# connectors.net
KiCad netlist of a schematic drawn in Altium Designer
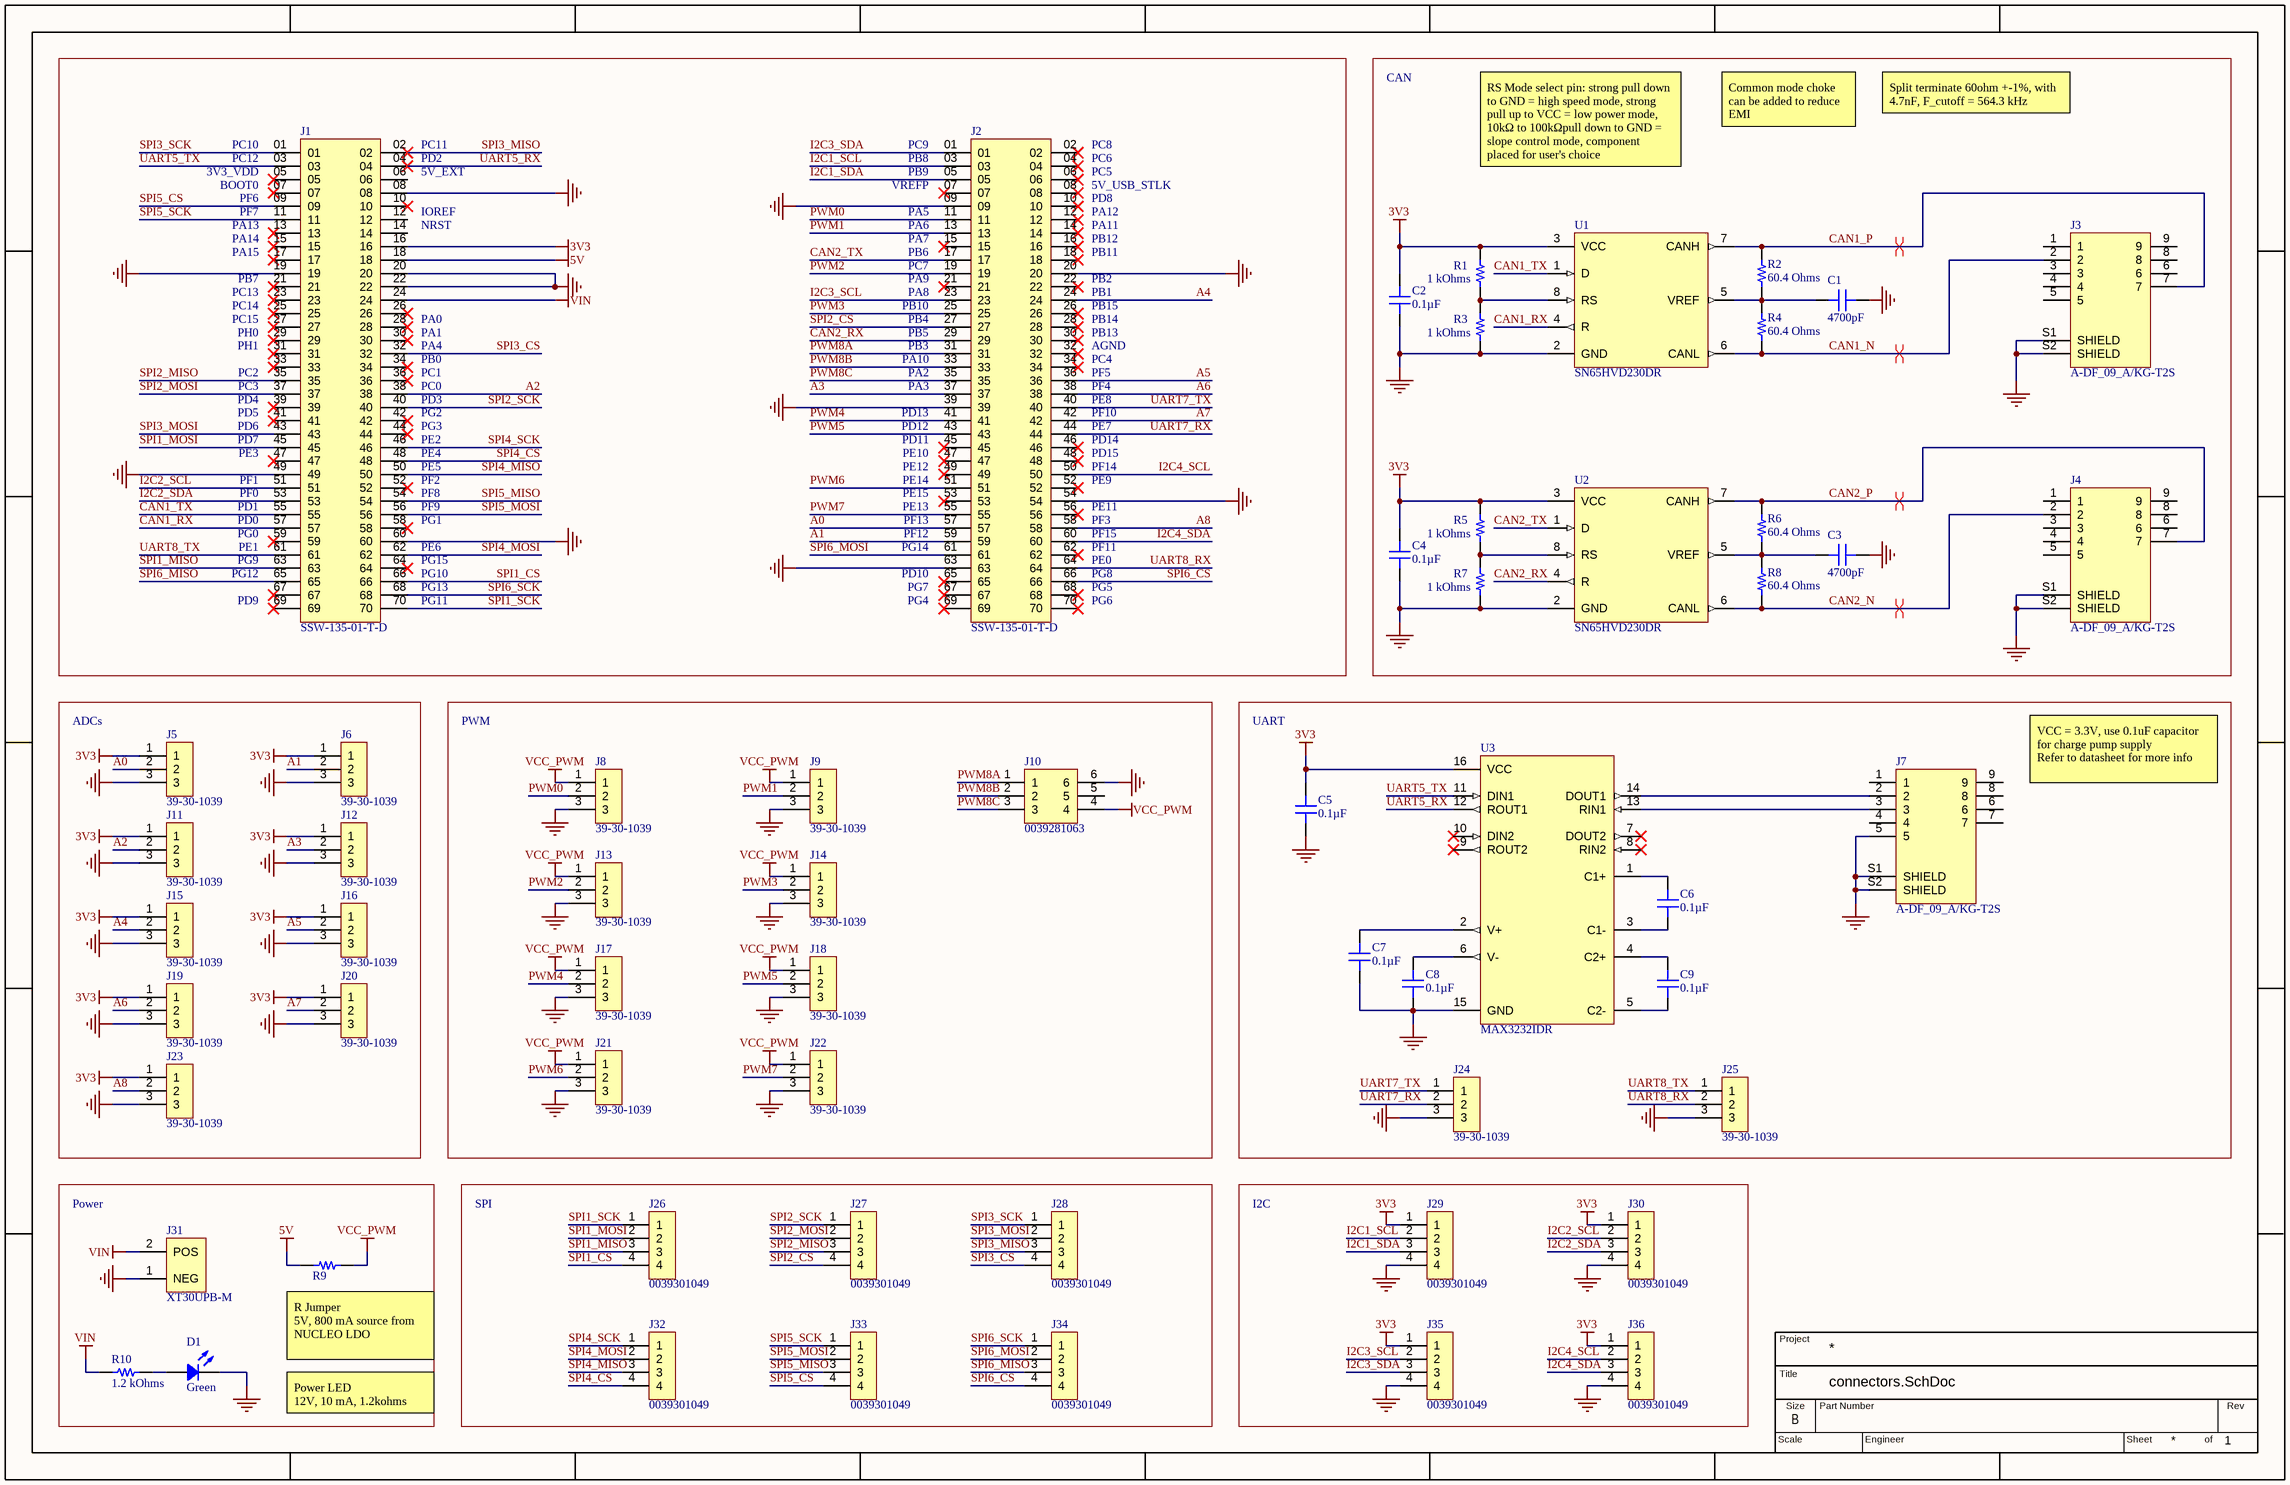
[diagram p0: connectors.SchDoc]

(export (version "E")
  (design (tool "Eeschema 10.0.6"))
  (components
    (comp (ref "C1")
      (value "4700pF")
      (footprint "CAP 0603_1608")
      (description "CAP CER 4700PF 50V X7R 0603")
      (fields
        (field (name "PART NUMBER") "CGA3E2X7R1H472K080AA")
        (field (name "MANUFACTURER") "TDK Corporation")
      )
      (libsource (lib "Celestial Altium Library - altium_library") (part "Capacitor"))
    )
    (comp (ref "C2")
      (value "0.1µF")
      (footprint "CAP 0603_1608")
      (description "CAP CER 0.1UF 25V X7R 0603")
      (fields
        (field (name "PART NUMBER") "CL10B104KA8NNNC")
        (field (name "MANUFACTURER") "Samsung Electro-Mechanics")
      )
      (libsource (lib "Celestial Altium Library - altium_library") (part "Capacitor"))
    )
    (comp (ref "C3")
      (value "4700pF")
      (footprint "CAP 0603_1608")
      (description "CAP CER 4700PF 50V X7R 0603")
      (fields
        (field (name "PART NUMBER") "CGA3E2X7R1H472K080AA")
        (field (name "MANUFACTURER") "TDK Corporation")
      )
      (libsource (lib "Celestial Altium Library - altium_library") (part "Capacitor"))
    )
    (comp (ref "C4")
      (value "0.1µF")
      (footprint "CAP 0603_1608")
      (description "CAP CER 0.1UF 25V X7R 0603")
      (fields
        (field (name "PART NUMBER") "CL10B104KA8NNNC")
        (field (name "MANUFACTURER") "Samsung Electro-Mechanics")
      )
      (libsource (lib "Celestial Altium Library - altium_library") (part "Capacitor"))
    )
    (comp (ref "C5")
      (value "0.1µF")
      (footprint "CAP 0603_1608")
      (description "CAP CER 0.1UF 25V X7R 0603")
      (fields
        (field (name "PART NUMBER") "CL10B104KA8NNNC")
        (field (name "MANUFACTURER") "Samsung Electro-Mechanics")
      )
      (libsource (lib "Celestial Altium Library - altium_library") (part "Capacitor"))
    )
    (comp (ref "C6")
      (value "0.1µF")
      (footprint "CAP 0603_1608")
      (description "CAP CER 0.1UF 25V X7R 0603")
      (fields
        (field (name "PART NUMBER") "CL10B104KA8NNNC")
        (field (name "MANUFACTURER") "Samsung Electro-Mechanics")
      )
      (libsource (lib "Celestial Altium Library - altium_library") (part "Capacitor"))
    )
    (comp (ref "C7")
      (value "0.1µF")
      (footprint "CAP 0603_1608")
      (description "CAP CER 0.1UF 25V X7R 0603")
      (fields
        (field (name "PART NUMBER") "CL10B104KA8NNNC")
        (field (name "MANUFACTURER") "Samsung Electro-Mechanics")
      )
      (libsource (lib "Celestial Altium Library - altium_library") (part "Capacitor"))
    )
    (comp (ref "C8")
      (value "0.1µF")
      (footprint "CAP 0603_1608")
      (description "CAP CER 0.1UF 25V X7R 0603")
      (fields
        (field (name "PART NUMBER") "CL10B104KA8NNNC")
        (field (name "MANUFACTURER") "Samsung Electro-Mechanics")
      )
      (libsource (lib "Celestial Altium Library - altium_library") (part "Capacitor"))
    )
    (comp (ref "C9")
      (value "0.1µF")
      (footprint "CAP 0603_1608")
      (description "CAP CER 0.1UF 25V X7R 0603")
      (fields
        (field (name "PART NUMBER") "CL10B104KA8NNNC")
        (field (name "MANUFACTURER") "Samsung Electro-Mechanics")
      )
      (libsource (lib "Celestial Altium Library - altium_library") (part "Capacitor"))
    )
    (comp (ref "D1")
      (value "Green")
      (footprint "LED 0805_2012 GREEN")
      (description "LED GREEN CLEAR SMD")
      (fields (field (name "PART NUMBER") "LTST-C170GKT") (field (name "MANUFACTURER") "Lite-On Inc."))
      (libsource (lib "Celestial Altium Library - altium_library") (part "LED"))
    )
    (comp (ref "J1")
      (value "SSW-135-01-T-D")
      (footprint "SAMTEC_SSW-135-01-T-D")
      (fields (field (name "MF") "Samtec"))
      (libsource (lib "ertc_symbols") (part "SSW-135-01-T-D"))
    )
    (comp (ref "J2")
      (value "SSW-135-01-T-D")
      (footprint "SAMTEC_SSW-135-01-T-D")
      (fields (field (name "MF") "Samtec"))
      (libsource (lib "ertc_symbols") (part "SSW-135-01-T-D"))
    )
    (comp (ref "J3")
      (value "A-DF_09_A/KG-T2S")
      (footprint "ASSMANN_A-DF09A/KG-T2S")
      (description "9 Position D-Sub Receptacle, Female Sockets Connector")
      (fields (field (name "MP") "A-DF 09 A/KG-T2S") (field (name "MF") "Assmann WSW"))
      (libsource (lib "ertc_symbols") (part "A-DF_09_A/KG-T2S"))
    )
    (comp (ref "J4")
      (value "A-DF_09_A/KG-T2S")
      (footprint "ASSMANN_A-DF09A/KG-T2S")
      (description "9 Position D-Sub Receptacle, Female Sockets Connector")
      (fields (field (name "MP") "A-DF 09 A/KG-T2S") (field (name "MF") "Assmann WSW"))
      (libsource (lib "ertc_symbols") (part "A-DF_09_A/KG-T2S"))
    )
    (comp (ref "J5")
      (value "39-30-1039")
      (footprint "MOLEX_39-30-1039")
      (description "Connector Header Through Hole 3 position 0.165 _4.20mm_")
      (fields (field (name "MP") "39301039") (field (name "MF") "Molex"))
      (libsource (lib "ertc_symbols") (part "39-30-1039"))
    )
    (comp (ref "J6")
      (value "39-30-1039")
      (footprint "MOLEX_39-30-1039")
      (description "Connector Header Through Hole 3 position 0.165 _4.20mm_")
      (fields (field (name "MP") "39301039") (field (name "MF") "Molex"))
      (libsource (lib "ertc_symbols") (part "39-30-1039"))
    )
    (comp (ref "J7")
      (value "A-DF_09_A/KG-T2S")
      (footprint "ASSMANN_A-DF09A/KG-T2S")
      (description "9 Position D-Sub Receptacle, Female Sockets Connector")
      (fields (field (name "MP") "A-DF 09 A/KG-T2S") (field (name "MF") "Assmann WSW"))
      (libsource (lib "ertc_symbols") (part "A-DF_09_A/KG-T2S"))
    )
    (comp (ref "J8")
      (value "39-30-1039")
      (footprint "MOLEX_39-30-1039")
      (description "Connector Header Through Hole 3 position 0.165 _4.20mm_")
      (fields (field (name "MP") "39301039") (field (name "MF") "Molex"))
      (libsource (lib "ertc_symbols") (part "39-30-1039"))
    )
    (comp (ref "J9")
      (value "39-30-1039")
      (footprint "MOLEX_39-30-1039")
      (description "Connector Header Through Hole 3 position 0.165 _4.20mm_")
      (fields (field (name "MP") "39301039") (field (name "MF") "Molex"))
      (libsource (lib "ertc_symbols") (part "39-30-1039"))
    )
    (comp (ref "J10")
      (value "0039281063")
      (footprint "MOLEX_0039281063")
      (description "Connector Header Through Hole, 6 position 0.165 (4.20mm)")
      (fields (field (name "MP") "0026013115") (field (name "MF") "Molex"))
      (libsource (lib "ertc_symbols") (part "0039281063"))
    )
    (comp (ref "J11")
      (value "39-30-1039")
      (footprint "MOLEX_39-30-1039")
      (description "Connector Header Through Hole 3 position 0.165 _4.20mm_")
      (fields (field (name "MP") "39301039") (field (name "MF") "Molex"))
      (libsource (lib "ertc_symbols") (part "39-30-1039"))
    )
    (comp (ref "J12")
      (value "39-30-1039")
      (footprint "MOLEX_39-30-1039")
      (description "Connector Header Through Hole 3 position 0.165 _4.20mm_")
      (fields (field (name "MP") "39301039") (field (name "MF") "Molex"))
      (libsource (lib "ertc_symbols") (part "39-30-1039"))
    )
    (comp (ref "J13")
      (value "39-30-1039")
      (footprint "MOLEX_39-30-1039")
      (description "Connector Header Through Hole 3 position 0.165 _4.20mm_")
      (fields (field (name "MP") "39301039") (field (name "MF") "Molex"))
      (libsource (lib "ertc_symbols") (part "39-30-1039"))
    )
    (comp (ref "J14")
      (value "39-30-1039")
      (footprint "MOLEX_39-30-1039")
      (description "Connector Header Through Hole 3 position 0.165 _4.20mm_")
      (fields (field (name "MP") "39301039") (field (name "MF") "Molex"))
      (libsource (lib "ertc_symbols") (part "39-30-1039"))
    )
    (comp (ref "J15")
      (value "39-30-1039")
      (footprint "MOLEX_39-30-1039")
      (description "Connector Header Through Hole 3 position 0.165 _4.20mm_")
      (fields (field (name "MP") "39301039") (field (name "MF") "Molex"))
      (libsource (lib "ertc_symbols") (part "39-30-1039"))
    )
    (comp (ref "J16")
      (value "39-30-1039")
      (footprint "MOLEX_39-30-1039")
      (description "Connector Header Through Hole 3 position 0.165 _4.20mm_")
      (fields (field (name "MP") "39301039") (field (name "MF") "Molex"))
      (libsource (lib "ertc_symbols") (part "39-30-1039"))
    )
    (comp (ref "J17")
      (value "39-30-1039")
      (footprint "MOLEX_39-30-1039")
      (description "Connector Header Through Hole 3 position 0.165 _4.20mm_")
      (fields (field (name "MP") "39301039") (field (name "MF") "Molex"))
      (libsource (lib "ertc_symbols") (part "39-30-1039"))
    )
    (comp (ref "J18")
      (value "39-30-1039")
      (footprint "MOLEX_39-30-1039")
      (description "Connector Header Through Hole 3 position 0.165 _4.20mm_")
      (fields (field (name "MP") "39301039") (field (name "MF") "Molex"))
      (libsource (lib "ertc_symbols") (part "39-30-1039"))
    )
    (comp (ref "J19")
      (value "39-30-1039")
      (footprint "MOLEX_39-30-1039")
      (description "Connector Header Through Hole 3 position 0.165 _4.20mm_")
      (fields (field (name "MP") "39301039") (field (name "MF") "Molex"))
      (libsource (lib "ertc_symbols") (part "39-30-1039"))
    )
    (comp (ref "J20")
      (value "39-30-1039")
      (footprint "MOLEX_39-30-1039")
      (description "Connector Header Through Hole 3 position 0.165 _4.20mm_")
      (fields (field (name "MP") "39301039") (field (name "MF") "Molex"))
      (libsource (lib "ertc_symbols") (part "39-30-1039"))
    )
    (comp (ref "J21")
      (value "39-30-1039")
      (footprint "MOLEX_39-30-1039")
      (description "Connector Header Through Hole 3 position 0.165 _4.20mm_")
      (fields (field (name "MP") "39301039") (field (name "MF") "Molex"))
      (libsource (lib "ertc_symbols") (part "39-30-1039"))
    )
    (comp (ref "J22")
      (value "39-30-1039")
      (footprint "MOLEX_39-30-1039")
      (description "Connector Header Through Hole 3 position 0.165 _4.20mm_")
      (fields (field (name "MP") "39301039") (field (name "MF") "Molex"))
      (libsource (lib "ertc_symbols") (part "39-30-1039"))
    )
    (comp (ref "J23")
      (value "39-30-1039")
      (footprint "MOLEX_39-30-1039")
      (description "Connector Header Through Hole 3 position 0.165 _4.20mm_")
      (fields (field (name "MP") "39301039") (field (name "MF") "Molex"))
      (libsource (lib "ertc_symbols") (part "39-30-1039"))
    )
    (comp (ref "J24")
      (value "39-30-1039")
      (footprint "MOLEX_39-30-1039")
      (description "Connector Header Through Hole 3 position 0.165 _4.20mm_")
      (fields (field (name "MP") "39301039") (field (name "MF") "Molex"))
      (libsource (lib "ertc_symbols") (part "39-30-1039"))
    )
    (comp (ref "J25")
      (value "39-30-1039")
      (footprint "MOLEX_39-30-1039")
      (description "Connector Header Through Hole 3 position 0.165 _4.20mm_")
      (fields (field (name "MP") "39301039") (field (name "MF") "Molex"))
      (libsource (lib "ertc_symbols") (part "39-30-1039"))
    )
    (comp (ref "J26")
      (value "0039301049")
      (footprint "MOLEX_0039301049")
      (description "Connector Header Through Hole 4 position 0.165 _4.20mm_")
      (fields (field (name "MF") "Molex"))
      (libsource (lib "ertc_symbols") (part "0039301049"))
    )
    (comp (ref "J27")
      (value "0039301049")
      (footprint "MOLEX_0039301049")
      (description "Connector Header Through Hole 4 position 0.165 _4.20mm_")
      (fields (field (name "MF") "Molex"))
      (libsource (lib "ertc_symbols") (part "0039301049"))
    )
    (comp (ref "J28")
      (value "0039301049")
      (footprint "MOLEX_0039301049")
      (description "Connector Header Through Hole 4 position 0.165 _4.20mm_")
      (fields (field (name "MF") "Molex"))
      (libsource (lib "ertc_symbols") (part "0039301049"))
    )
    (comp (ref "J29")
      (value "0039301049")
      (footprint "MOLEX_0039301049")
      (description "Connector Header Through Hole 4 position 0.165 _4.20mm_")
      (fields (field (name "MF") "Molex"))
      (libsource (lib "ertc_symbols") (part "0039301049"))
    )
    (comp (ref "J30")
      (value "0039301049")
      (footprint "MOLEX_0039301049")
      (description "Connector Header Through Hole 4 position 0.165 _4.20mm_")
      (fields (field (name "MF") "Molex"))
      (libsource (lib "ertc_symbols") (part "0039301049"))
    )
    (comp (ref "J31")
      (value "XT30UPB-M")
      (footprint "AMASS_XT30-M")
      (description "Plug; DC supply; XT60; male; PIN: 2; for cable; soldered; 30A; 500V")
      (fields (field (name "MP") "XT60-M") (field (name "MF") "AMASS"))
      (libsource (lib "ertc_symbols") (part "XT30UPB-M"))
    )
    (comp (ref "J32")
      (value "0039301049")
      (footprint "MOLEX_0039301049")
      (description "Connector Header Through Hole 4 position 0.165 _4.20mm_")
      (fields (field (name "MF") "Molex"))
      (libsource (lib "ertc_symbols") (part "0039301049"))
    )
    (comp (ref "J33")
      (value "0039301049")
      (footprint "MOLEX_0039301049")
      (description "Connector Header Through Hole 4 position 0.165 _4.20mm_")
      (fields (field (name "MF") "Molex"))
      (libsource (lib "ertc_symbols") (part "0039301049"))
    )
    (comp (ref "J34")
      (value "0039301049")
      (footprint "MOLEX_0039301049")
      (description "Connector Header Through Hole 4 position 0.165 _4.20mm_")
      (fields (field (name "MF") "Molex"))
      (libsource (lib "ertc_symbols") (part "0039301049"))
    )
    (comp (ref "J35")
      (value "0039301049")
      (footprint "MOLEX_0039301049")
      (description "Connector Header Through Hole 4 position 0.165 _4.20mm_")
      (fields (field (name "MF") "Molex"))
      (libsource (lib "ertc_symbols") (part "0039301049"))
    )
    (comp (ref "J36")
      (value "0039301049")
      (footprint "MOLEX_0039301049")
      (description "Connector Header Through Hole 4 position 0.165 _4.20mm_")
      (fields (field (name "MF") "Molex"))
      (libsource (lib "ertc_symbols") (part "0039301049"))
    )
    (comp (ref "R1")
      (value "1 kOhms")
      (footprint "RES 0805_2012")
      (description "RES 1K OHM 1% 1/4W 0805")
      (fields
        (field (name "PART NUMBER") "RNCP0805FTD1K00")
        (field (name "MANUFACTURER") "Stackpole Electronics Inc")
      )
      (libsource (lib "Celestial Altium Library - altium_library") (part "Resistor"))
    )
    (comp (ref "R2")
      (value "60.4 Ohms")
      (footprint "RES 0603_1608")
      (description "RES 60.4 OHM 1% 1/10W 0603")
      (fields
        (field (name "PART NUMBER") "RMCF0603FT60R4")
        (field (name "MANUFACTURER") "Stackpole Electronics Inc")
      )
      (libsource (lib "Celestial Altium Library - altium_library") (part "Resistor"))
    )
    (comp (ref "R3")
      (value "1 kOhms")
      (footprint "RES 0805_2012")
      (description "RES 1K OHM 1% 1/4W 0805")
      (fields
        (field (name "PART NUMBER") "RNCP0805FTD1K00")
        (field (name "MANUFACTURER") "Stackpole Electronics Inc")
      )
      (libsource (lib "Celestial Altium Library - altium_library") (part "Resistor"))
    )
    (comp (ref "R4")
      (value "60.4 Ohms")
      (footprint "RES 0603_1608")
      (description "RES 60.4 OHM 1% 1/10W 0603")
      (fields
        (field (name "PART NUMBER") "RMCF0603FT60R4")
        (field (name "MANUFACTURER") "Stackpole Electronics Inc")
      )
      (libsource (lib "Celestial Altium Library - altium_library") (part "Resistor"))
    )
    (comp (ref "R5")
      (value "1 kOhms")
      (footprint "RES 0805_2012")
      (description "RES 1K OHM 1% 1/4W 0805")
      (fields
        (field (name "PART NUMBER") "RNCP0805FTD1K00")
        (field (name "MANUFACTURER") "Stackpole Electronics Inc")
      )
      (libsource (lib "Celestial Altium Library - altium_library") (part "Resistor"))
    )
    (comp (ref "R6")
      (value "60.4 Ohms")
      (footprint "RES 0603_1608")
      (description "RES 60.4 OHM 1% 1/10W 0603")
      (fields
        (field (name "PART NUMBER") "RMCF0603FT60R4")
        (field (name "MANUFACTURER") "Stackpole Electronics Inc")
      )
      (libsource (lib "Celestial Altium Library - altium_library") (part "Resistor"))
    )
    (comp (ref "R7")
      (value "1 kOhms")
      (footprint "RES 0805_2012")
      (description "RES 1K OHM 1% 1/4W 0805")
      (fields
        (field (name "PART NUMBER") "RNCP0805FTD1K00")
        (field (name "MANUFACTURER") "Stackpole Electronics Inc")
      )
      (libsource (lib "Celestial Altium Library - altium_library") (part "Resistor"))
    )
    (comp (ref "R8")
      (value "60.4 Ohms")
      (footprint "RES 0603_1608")
      (description "RES 60.4 OHM 1% 1/10W 0603")
      (fields
        (field (name "PART NUMBER") "RMCF0603FT60R4")
        (field (name "MANUFACTURER") "Stackpole Electronics Inc")
      )
      (libsource (lib "Celestial Altium Library - altium_library") (part "Resistor"))
    )
    (comp (ref "R9")
      (value "~")
      (footprint "RES 0603_1608")
      (description "RES SMD 0 OHM JUMP 1/10W 0603")
      (fields (field (name "PART NUMBER") "CRCW06030000Z0EBC") (field (name "MANUFACTURER") "Vishay Dale"))
      (libsource (lib "Celestial Altium Library - altium_library") (part "Resistor"))
    )
    (comp (ref "R10")
      (value "1.2 kOhms")
      (footprint "RES 0603_1608")
      (description "CRGCQ 0603 1K2 1%")
      (fields
        (field (name "PART NUMBER") "CRGCQ0603F1K2")
        (field (name "MANUFACTURER") "TE Connectivity Passive Product")
      )
      (libsource (lib "Celestial Altium Library - altium_library") (part "Resistor"))
    )
    (comp (ref "U1")
      (value "SN65HVD230DR")
      (footprint "SOIC127P599X175-8N")
      (description "3.3 V CAN Transceiver with Standby Mode 8-SOIC -40 to 85")
      (fields (field (name "MF") "Texas Instruments"))
      (libsource (lib "ertc_symbols") (part "SN65HVD230DR"))
    )
    (comp (ref "U2")
      (value "SN65HVD230DR")
      (footprint "SOIC127P599X175-8N")
      (description "3.3 V CAN Transceiver with Standby Mode 8-SOIC -40 to 85")
      (fields (field (name "MF") "Texas Instruments"))
      (libsource (lib "ertc_symbols") (part "SN65HVD230DR"))
    )
    (comp (ref "U3")
      (value "MAX3232IDR")
      (footprint "SOIC127P600X175-16N")
      (description "3-V to 5.5-V multichannel RS-232 line driver & receiver 16-SOIC -40 to 85")
      (fields (field (name "MF") "Texas Instruments") (field (name "DIGI-KEY_PART_NUMBER") "296-13098-1-ND"))
      (libsource (lib "ertc_symbols") (part "MAX3232IDR"))
    )
  )
  (nets
    (net (code "2") (name "/A0") (class "Default")
      (node (ref "J2") (pin "57") (pinfunction "57_57") (pintype "passive"))
      (node (ref "J5") (pin "2") (pinfunction "2_2") (pintype "passive"))
    )
    (net (code "3") (name "/A1") (class "Default")
      (node (ref "J2") (pin "59") (pinfunction "59_59") (pintype "passive"))
      (node (ref "J6") (pin "2") (pinfunction "2_2") (pintype "passive"))
    )
    (net (code "4") (name "/A2") (class "Default")
      (node (ref "J1") (pin "38") (pinfunction "38_38") (pintype "passive"))
      (node (ref "J11") (pin "2") (pinfunction "2_2") (pintype "passive"))
    )
    (net (code "5") (name "/A3") (class "Default")
      (node (ref "J12") (pin "2") (pinfunction "2_2") (pintype "passive"))
      (node (ref "J2") (pin "37") (pinfunction "37_37") (pintype "passive"))
    )
    (net (code "6") (name "/A4") (class "Default")
      (node (ref "J15") (pin "2") (pinfunction "2_2") (pintype "passive"))
      (node (ref "J2") (pin "24") (pinfunction "24_24") (pintype "passive"))
    )
    (net (code "7") (name "/A5") (class "Default")
      (node (ref "J16") (pin "2") (pinfunction "2_2") (pintype "passive"))
      (node (ref "J2") (pin "36") (pinfunction "36_36") (pintype "passive"))
    )
    (net (code "8") (name "/A6") (class "Default")
      (node (ref "J19") (pin "2") (pinfunction "2_2") (pintype "passive"))
      (node (ref "J2") (pin "38") (pinfunction "38_38") (pintype "passive"))
    )
    (net (code "9") (name "/A7") (class "Default")
      (node (ref "J2") (pin "42") (pinfunction "42_42") (pintype "passive"))
      (node (ref "J20") (pin "2") (pinfunction "2_2") (pintype "passive"))
    )
    (net (code "10") (name "/A8") (class "Default")
      (node (ref "J2") (pin "58") (pinfunction "58_58") (pintype "passive"))
      (node (ref "J23") (pin "2") (pinfunction "2_2") (pintype "passive"))
    )
    (net (code "11") (name "/CAN1_N") (class "Default")
      (node (ref "J3") (pin "2") (pinfunction "2_2") (pintype "passive"))
      (node (ref "R4") (pin "2") (pinfunction "2_2") (pintype "passive"))
      (node (ref "U1") (pin "6") (pinfunction "CANL_6") (pintype "output"))
    )
    (net (code "12") (name "/CAN1_P") (class "Default")
      (node (ref "J3") (pin "7") (pinfunction "7_7") (pintype "passive"))
      (node (ref "R2") (pin "1") (pinfunction "1_1") (pintype "passive"))
      (node (ref "U1") (pin "7") (pinfunction "CANH_7") (pintype "output"))
    )
    (net (code "13") (name "/CAN1_RX") (class "Default")
      (node (ref "J1") (pin "57") (pinfunction "57_57") (pintype "passive"))
      (node (ref "U1") (pin "4") (pinfunction "R_4") (pintype "output"))
    )
    (net (code "14") (name "/CAN1_TX") (class "Default")
      (node (ref "J1") (pin "55") (pinfunction "55_55") (pintype "passive"))
      (node (ref "U1") (pin "1") (pinfunction "D_1") (pintype "input"))
    )
    (net (code "15") (name "/CAN2_N") (class "Default")
      (node (ref "J4") (pin "2") (pinfunction "2_2") (pintype "passive"))
      (node (ref "R8") (pin "2") (pinfunction "2_2") (pintype "passive"))
      (node (ref "U2") (pin "6") (pinfunction "CANL_6") (pintype "output"))
    )
    (net (code "16") (name "/CAN2_P") (class "Default")
      (node (ref "J4") (pin "7") (pinfunction "7_7") (pintype "passive"))
      (node (ref "R6") (pin "1") (pinfunction "1_1") (pintype "passive"))
      (node (ref "U2") (pin "7") (pinfunction "CANH_7") (pintype "output"))
    )
    (net (code "17") (name "/CAN2_RX") (class "Default")
      (node (ref "J2") (pin "29") (pinfunction "29_29") (pintype "passive"))
      (node (ref "U2") (pin "4") (pinfunction "R_4") (pintype "output"))
    )
    (net (code "18") (name "/CAN2_TX") (class "Default")
      (node (ref "J2") (pin "17") (pinfunction "17_17") (pintype "passive"))
      (node (ref "U2") (pin "1") (pinfunction "D_1") (pintype "input"))
    )
    (net (code "19") (name "/I2C1_SCL") (class "Default")
      (node (ref "J2") (pin "03") (pinfunction "03_03") (pintype "passive"))
      (node (ref "J29") (pin "2") (pinfunction "2_2") (pintype "passive"))
    )
    (net (code "20") (name "/I2C1_SDA") (class "Default")
      (node (ref "J2") (pin "05") (pinfunction "05_05") (pintype "passive"))
      (node (ref "J29") (pin "3") (pinfunction "3_3") (pintype "passive"))
    )
    (net (code "21") (name "/I2C2_SCL") (class "Default")
      (node (ref "J1") (pin "51") (pinfunction "51_51") (pintype "passive"))
      (node (ref "J30") (pin "2") (pinfunction "2_2") (pintype "passive"))
    )
    (net (code "22") (name "/I2C2_SDA") (class "Default")
      (node (ref "J1") (pin "53") (pinfunction "53_53") (pintype "passive"))
      (node (ref "J30") (pin "3") (pinfunction "3_3") (pintype "passive"))
    )
    (net (code "23") (name "/I2C3_SCL") (class "Default")
      (node (ref "J2") (pin "23") (pinfunction "23_23") (pintype "passive"))
      (node (ref "J35") (pin "2") (pinfunction "2_2") (pintype "passive"))
    )
    (net (code "24") (name "/I2C3_SDA") (class "Default")
      (node (ref "J2") (pin "01") (pinfunction "01_01") (pintype "passive"))
      (node (ref "J35") (pin "3") (pinfunction "3_3") (pintype "passive"))
    )
    (net (code "25") (name "/I2C4_SCL") (class "Default")
      (node (ref "J2") (pin "50") (pinfunction "50_50") (pintype "passive"))
      (node (ref "J36") (pin "2") (pinfunction "2_2") (pintype "passive"))
    )
    (net (code "26") (name "/I2C4_SDA") (class "Default")
      (node (ref "J2") (pin "60") (pinfunction "60_60") (pintype "passive"))
      (node (ref "J36") (pin "3") (pinfunction "3_3") (pintype "passive"))
    )
    (net (code "27") (name "/PWM0") (class "Default")
      (node (ref "J2") (pin "11") (pinfunction "11_11") (pintype "passive"))
      (node (ref "J8") (pin "2") (pinfunction "2_2") (pintype "passive"))
    )
    (net (code "28") (name "/PWM1") (class "Default")
      (node (ref "J2") (pin "13") (pinfunction "13_13") (pintype "passive"))
      (node (ref "J9") (pin "2") (pinfunction "2_2") (pintype "passive"))
    )
    (net (code "29") (name "/PWM2") (class "Default")
      (node (ref "J13") (pin "2") (pinfunction "2_2") (pintype "passive"))
      (node (ref "J2") (pin "19") (pinfunction "19_19") (pintype "passive"))
    )
    (net (code "30") (name "/PWM3") (class "Default")
      (node (ref "J14") (pin "2") (pinfunction "2_2") (pintype "passive"))
      (node (ref "J2") (pin "25") (pinfunction "25_25") (pintype "passive"))
    )
    (net (code "31") (name "/PWM4") (class "Default")
      (node (ref "J17") (pin "2") (pinfunction "2_2") (pintype "passive"))
      (node (ref "J2") (pin "41") (pinfunction "41_41") (pintype "passive"))
    )
    (net (code "32") (name "/PWM5") (class "Default")
      (node (ref "J18") (pin "2") (pinfunction "2_2") (pintype "passive"))
      (node (ref "J2") (pin "43") (pinfunction "43_43") (pintype "passive"))
    )
    (net (code "33") (name "/PWM6") (class "Default")
      (node (ref "J2") (pin "51") (pinfunction "51_51") (pintype "passive"))
      (node (ref "J21") (pin "2") (pinfunction "2_2") (pintype "passive"))
    )
    (net (code "34") (name "/PWM7") (class "Default")
      (node (ref "J2") (pin "55") (pinfunction "55_55") (pintype "passive"))
      (node (ref "J22") (pin "2") (pinfunction "2_2") (pintype "passive"))
    )
    (net (code "35") (name "/PWM8A") (class "Default")
      (node (ref "J10") (pin "1") (pinfunction "1_1") (pintype "passive"))
      (node (ref "J2") (pin "31") (pinfunction "31_31") (pintype "passive"))
    )
    (net (code "36") (name "/PWM8B") (class "Default")
      (node (ref "J10") (pin "2") (pinfunction "2_2") (pintype "passive"))
      (node (ref "J2") (pin "33") (pinfunction "33_33") (pintype "passive"))
    )
    (net (code "37") (name "/PWM8C") (class "Default")
      (node (ref "J10") (pin "3") (pinfunction "3_3") (pintype "passive"))
      (node (ref "J2") (pin "35") (pinfunction "35_35") (pintype "passive"))
    )
    (net (code "38") (name "/SPI1_CS") (class "Default")
      (node (ref "J1") (pin "66") (pinfunction "66_66") (pintype "passive"))
      (node (ref "J26") (pin "4") (pinfunction "4_4") (pintype "passive"))
    )
    (net (code "39") (name "/SPI1_MISO") (class "Default")
      (node (ref "J1") (pin "63") (pinfunction "63_63") (pintype "passive"))
      (node (ref "J26") (pin "3") (pinfunction "3_3") (pintype "passive"))
    )
    (net (code "40") (name "/SPI1_MOSI") (class "Default")
      (node (ref "J1") (pin "45") (pinfunction "45_45") (pintype "passive"))
      (node (ref "J26") (pin "2") (pinfunction "2_2") (pintype "passive"))
    )
    (net (code "41") (name "/SPI1_SCK") (class "Default")
      (node (ref "J1") (pin "70") (pinfunction "70_70") (pintype "passive"))
      (node (ref "J26") (pin "1") (pinfunction "1_1") (pintype "passive"))
    )
    (net (code "42") (name "/SPI2_CS") (class "Default")
      (node (ref "J2") (pin "27") (pinfunction "27_27") (pintype "passive"))
      (node (ref "J27") (pin "4") (pinfunction "4_4") (pintype "passive"))
    )
    (net (code "43") (name "/SPI2_MISO") (class "Default")
      (node (ref "J1") (pin "35") (pinfunction "35_35") (pintype "passive"))
      (node (ref "J27") (pin "3") (pinfunction "3_3") (pintype "passive"))
    )
    (net (code "44") (name "/SPI2_MOSI") (class "Default")
      (node (ref "J1") (pin "37") (pinfunction "37_37") (pintype "passive"))
      (node (ref "J27") (pin "2") (pinfunction "2_2") (pintype "passive"))
    )
    (net (code "45") (name "/SPI2_SCK") (class "Default")
      (node (ref "J1") (pin "40") (pinfunction "40_40") (pintype "passive"))
      (node (ref "J27") (pin "1") (pinfunction "1_1") (pintype "passive"))
    )
    (net (code "46") (name "/SPI3_CS") (class "Default")
      (node (ref "J1") (pin "32") (pinfunction "32_32") (pintype "passive"))
      (node (ref "J28") (pin "4") (pinfunction "4_4") (pintype "passive"))
    )
    (net (code "47") (name "/SPI3_MISO") (class "Default")
      (node (ref "J1") (pin "02") (pinfunction "02_02") (pintype "passive"))
      (node (ref "J28") (pin "3") (pinfunction "3_3") (pintype "passive"))
    )
    (net (code "48") (name "/SPI3_MOSI") (class "Default")
      (node (ref "J1") (pin "43") (pinfunction "43_43") (pintype "passive"))
      (node (ref "J28") (pin "2") (pinfunction "2_2") (pintype "passive"))
    )
    (net (code "49") (name "/SPI3_SCK") (class "Default")
      (node (ref "J1") (pin "01") (pinfunction "01_01") (pintype "passive"))
      (node (ref "J28") (pin "1") (pinfunction "1_1") (pintype "passive"))
    )
    (net (code "50") (name "/SPI4_CS") (class "Default")
      (node (ref "J1") (pin "48") (pinfunction "48_48") (pintype "passive"))
      (node (ref "J32") (pin "4") (pinfunction "4_4") (pintype "passive"))
    )
    (net (code "51") (name "/SPI4_MISO") (class "Default")
      (node (ref "J1") (pin "50") (pinfunction "50_50") (pintype "passive"))
      (node (ref "J32") (pin "3") (pinfunction "3_3") (pintype "passive"))
    )
    (net (code "52") (name "/SPI4_MOSI") (class "Default")
      (node (ref "J1") (pin "62") (pinfunction "62_62") (pintype "passive"))
      (node (ref "J32") (pin "2") (pinfunction "2_2") (pintype "passive"))
    )
    (net (code "53") (name "/SPI4_SCK") (class "Default")
      (node (ref "J1") (pin "46") (pinfunction "46_46") (pintype "passive"))
      (node (ref "J32") (pin "1") (pinfunction "1_1") (pintype "passive"))
    )
    (net (code "54") (name "/SPI5_CS") (class "Default")
      (node (ref "J1") (pin "09") (pinfunction "09_09") (pintype "passive"))
      (node (ref "J33") (pin "4") (pinfunction "4_4") (pintype "passive"))
    )
    (net (code "55") (name "/SPI5_MISO") (class "Default")
      (node (ref "J1") (pin "54") (pinfunction "54_54") (pintype "passive"))
      (node (ref "J33") (pin "3") (pinfunction "3_3") (pintype "passive"))
    )
    (net (code "56") (name "/SPI5_MOSI") (class "Default")
      (node (ref "J1") (pin "56") (pinfunction "56_56") (pintype "passive"))
      (node (ref "J33") (pin "2") (pinfunction "2_2") (pintype "passive"))
    )
    (net (code "57") (name "/SPI5_SCK") (class "Default")
      (node (ref "J1") (pin "11") (pinfunction "11_11") (pintype "passive"))
      (node (ref "J33") (pin "1") (pinfunction "1_1") (pintype "passive"))
    )
    (net (code "58") (name "/SPI6_CS") (class "Default")
      (node (ref "J2") (pin "66") (pinfunction "66_66") (pintype "passive"))
      (node (ref "J34") (pin "4") (pinfunction "4_4") (pintype "passive"))
    )
    (net (code "59") (name "/SPI6_MISO") (class "Default")
      (node (ref "J1") (pin "65") (pinfunction "65_65") (pintype "passive"))
      (node (ref "J34") (pin "3") (pinfunction "3_3") (pintype "passive"))
    )
    (net (code "60") (name "/SPI6_MOSI") (class "Default")
      (node (ref "J2") (pin "61") (pinfunction "61_61") (pintype "passive"))
      (node (ref "J34") (pin "2") (pinfunction "2_2") (pintype "passive"))
    )
    (net (code "61") (name "/SPI6_SCK") (class "Default")
      (node (ref "J1") (pin "68") (pinfunction "68_68") (pintype "passive"))
      (node (ref "J34") (pin "1") (pinfunction "1_1") (pintype "passive"))
    )
    (net (code "62") (name "/UART5_RX") (class "Default")
      (node (ref "J1") (pin "04") (pinfunction "04_04") (pintype "passive"))
      (node (ref "U3") (pin "12") (pinfunction "ROUT1_12") (pintype "output"))
    )
    (net (code "63") (name "/UART5_TX") (class "Default")
      (node (ref "J1") (pin "03") (pinfunction "03_03") (pintype "passive"))
      (node (ref "U3") (pin "11") (pinfunction "DIN1_11") (pintype "input"))
    )
    (net (code "64") (name "/UART7_RX") (class "Default")
      (node (ref "J2") (pin "44") (pinfunction "44_44") (pintype "passive"))
      (node (ref "J24") (pin "2") (pinfunction "2_2") (pintype "passive"))
    )
    (net (code "65") (name "/UART7_TX") (class "Default")
      (node (ref "J2") (pin "40") (pinfunction "40_40") (pintype "passive"))
      (node (ref "J24") (pin "1") (pinfunction "1_1") (pintype "passive"))
    )
    (net (code "66") (name "/UART8_RX") (class "Default")
      (node (ref "J2") (pin "64") (pinfunction "64_64") (pintype "passive"))
      (node (ref "J25") (pin "2") (pinfunction "2_2") (pintype "passive"))
    )
    (net (code "67") (name "/UART8_TX") (class "Default")
      (node (ref "J1") (pin "61") (pinfunction "61_61") (pintype "passive"))
      (node (ref "J25") (pin "1") (pinfunction "1_1") (pintype "passive"))
    )
    (net (code "68") (name "3V3") (class "Default")
      (node (ref "C2") (pin "2") (pinfunction "2_2") (pintype "passive"))
      (node (ref "C4") (pin "2") (pinfunction "2_2") (pintype "passive"))
      (node (ref "C5") (pin "2") (pinfunction "2_2") (pintype "passive"))
      (node (ref "J1") (pin "16") (pinfunction "16_16") (pintype "passive"))
      (node (ref "J11") (pin "1") (pinfunction "1_1") (pintype "passive"))
      (node (ref "J12") (pin "1") (pinfunction "1_1") (pintype "passive"))
      (node (ref "J15") (pin "1") (pinfunction "1_1") (pintype "passive"))
      (node (ref "J16") (pin "1") (pinfunction "1_1") (pintype "passive"))
      (node (ref "J19") (pin "1") (pinfunction "1_1") (pintype "passive"))
      (node (ref "J20") (pin "1") (pinfunction "1_1") (pintype "passive"))
      (node (ref "J23") (pin "1") (pinfunction "1_1") (pintype "passive"))
      (node (ref "J29") (pin "1") (pinfunction "1_1") (pintype "passive"))
      (node (ref "J30") (pin "1") (pinfunction "1_1") (pintype "passive"))
      (node (ref "J35") (pin "1") (pinfunction "1_1") (pintype "passive"))
      (node (ref "J36") (pin "1") (pinfunction "1_1") (pintype "passive"))
      (node (ref "J5") (pin "1") (pinfunction "1_1") (pintype "passive"))
      (node (ref "J6") (pin "1") (pinfunction "1_1") (pintype "passive"))
      (node (ref "R1") (pin "2") (pinfunction "2_2") (pintype "passive"))
      (node (ref "R5") (pin "2") (pinfunction "2_2") (pintype "passive"))
      (node (ref "U1") (pin "3") (pinfunction "VCC_3") (pintype "power_in"))
      (node (ref "U2") (pin "3") (pinfunction "VCC_3") (pintype "power_in"))
      (node (ref "U3") (pin "16") (pinfunction "VCC_16") (pintype "power_in"))
    )
    (net (code "69") (name "5V") (class "Default")
      (node (ref "J1") (pin "18") (pinfunction "18_18") (pintype "passive"))
      (node (ref "R9") (pin "1") (pinfunction "1_1") (pintype "passive"))
    )
    (net (code "70") (name "GND") (class "Default")
      (node (ref "C1") (pin "2") (pinfunction "2_2") (pintype "passive"))
      (node (ref "C2") (pin "1") (pinfunction "1_1") (pintype "passive"))
      (node (ref "C3") (pin "2") (pinfunction "2_2") (pintype "passive"))
      (node (ref "C4") (pin "1") (pinfunction "1_1") (pintype "passive"))
      (node (ref "C5") (pin "1") (pinfunction "1_1") (pintype "passive"))
      (node (ref "C7") (pin "1") (pinfunction "1_1") (pintype "passive"))
      (node (ref "C8") (pin "1") (pinfunction "1_1") (pintype "passive"))
      (node (ref "D1") (pin "2") (pinfunction "2_2") (pintype "passive"))
      (node (ref "J1") (pin "08") (pinfunction "08_08") (pintype "passive"))
      (node (ref "J1") (pin "19") (pinfunction "19_19") (pintype "passive"))
      (node (ref "J1") (pin "20") (pinfunction "20_20") (pintype "passive"))
      (node (ref "J1") (pin "22") (pinfunction "22_22") (pintype "passive"))
      (node (ref "J1") (pin "49") (pinfunction "49_49") (pintype "passive"))
      (node (ref "J1") (pin "60") (pinfunction "60_60") (pintype "passive"))
      (node (ref "J10") (pin "6") (pinfunction "6_6") (pintype "passive"))
      (node (ref "J11") (pin "3") (pinfunction "3_3") (pintype "passive"))
      (node (ref "J12") (pin "3") (pinfunction "3_3") (pintype "passive"))
      (node (ref "J13") (pin "3") (pinfunction "3_3") (pintype "passive"))
      (node (ref "J14") (pin "3") (pinfunction "3_3") (pintype "passive"))
      (node (ref "J15") (pin "3") (pinfunction "3_3") (pintype "passive"))
      (node (ref "J16") (pin "3") (pinfunction "3_3") (pintype "passive"))
      (node (ref "J17") (pin "3") (pinfunction "3_3") (pintype "passive"))
      (node (ref "J18") (pin "3") (pinfunction "3_3") (pintype "passive"))
      (node (ref "J19") (pin "3") (pinfunction "3_3") (pintype "passive"))
      (node (ref "J2") (pin "09") (pinfunction "09_09") (pintype "passive"))
      (node (ref "J2") (pin "20") (pinfunction "20_20") (pintype "passive"))
      (node (ref "J2") (pin "39") (pinfunction "39_39") (pintype "passive"))
      (node (ref "J2") (pin "54") (pinfunction "54_54") (pintype "passive"))
      (node (ref "J2") (pin "63") (pinfunction "63_63") (pintype "passive"))
      (node (ref "J20") (pin "3") (pinfunction "3_3") (pintype "passive"))
      (node (ref "J21") (pin "3") (pinfunction "3_3") (pintype "passive"))
      (node (ref "J22") (pin "3") (pinfunction "3_3") (pintype "passive"))
      (node (ref "J23") (pin "3") (pinfunction "3_3") (pintype "passive"))
      (node (ref "J24") (pin "3") (pinfunction "3_3") (pintype "passive"))
      (node (ref "J25") (pin "3") (pinfunction "3_3") (pintype "passive"))
      (node (ref "J29") (pin "4") (pinfunction "4_4") (pintype "passive"))
      (node (ref "J3") (pin "S1") (pinfunction "SHIELD_S1") (pintype "passive"))
      (node (ref "J3") (pin "S2") (pinfunction "SHIELD_S2") (pintype "passive"))
      (node (ref "J30") (pin "4") (pinfunction "4_4") (pintype "passive"))
      (node (ref "J31") (pin "1") (pinfunction "NEG_1") (pintype "passive"))
      (node (ref "J35") (pin "4") (pinfunction "4_4") (pintype "passive"))
      (node (ref "J36") (pin "4") (pinfunction "4_4") (pintype "passive"))
      (node (ref "J4") (pin "S1") (pinfunction "SHIELD_S1") (pintype "passive"))
      (node (ref "J4") (pin "S2") (pinfunction "SHIELD_S2") (pintype "passive"))
      (node (ref "J5") (pin "3") (pinfunction "3_3") (pintype "passive"))
      (node (ref "J6") (pin "3") (pinfunction "3_3") (pintype "passive"))
      (node (ref "J7") (pin "5") (pinfunction "5_5") (pintype "passive"))
      (node (ref "J7") (pin "S1") (pinfunction "SHIELD_S1") (pintype "passive"))
      (node (ref "J7") (pin "S2") (pinfunction "SHIELD_S2") (pintype "passive"))
      (node (ref "J8") (pin "3") (pinfunction "3_3") (pintype "passive"))
      (node (ref "J9") (pin "3") (pinfunction "3_3") (pintype "passive"))
      (node (ref "R3") (pin "1") (pinfunction "1_1") (pintype "passive"))
      (node (ref "R7") (pin "1") (pinfunction "1_1") (pintype "passive"))
      (node (ref "U1") (pin "2") (pinfunction "GND_2") (pintype "power_in"))
      (node (ref "U2") (pin "2") (pinfunction "GND_2") (pintype "power_in"))
      (node (ref "U3") (pin "15") (pinfunction "GND_15") (pintype "power_in"))
    )
    (net (code "71") (name "Net-(D1-Pad1)") (class "Default")
      (node (ref "D1") (pin "1") (pinfunction "1_1") (pintype "passive"))
      (node (ref "R10") (pin "2") (pinfunction "2_2") (pintype "passive"))
    )
    (net (code "72") (name "Net-(U1-RS)") (class "Default")
      (node (ref "R1") (pin "1") (pinfunction "1_1") (pintype "passive"))
      (node (ref "R3") (pin "2") (pinfunction "2_2") (pintype "passive"))
      (node (ref "U1") (pin "8") (pinfunction "RS_8") (pintype "input"))
    )
    (net (code "73") (name "Net-(U1-VREF)") (class "Default")
      (node (ref "C1") (pin "1") (pinfunction "1_1") (pintype "passive"))
      (node (ref "R2") (pin "2") (pinfunction "2_2") (pintype "passive"))
      (node (ref "R4") (pin "1") (pinfunction "1_1") (pintype "passive"))
      (node (ref "U1") (pin "5") (pinfunction "VREF_5") (pintype "output"))
    )
    (net (code "74") (name "Net-(U2-RS)") (class "Default")
      (node (ref "R5") (pin "1") (pinfunction "1_1") (pintype "passive"))
      (node (ref "R7") (pin "2") (pinfunction "2_2") (pintype "passive"))
      (node (ref "U2") (pin "8") (pinfunction "RS_8") (pintype "input"))
    )
    (net (code "75") (name "Net-(U2-VREF)") (class "Default")
      (node (ref "C3") (pin "1") (pinfunction "1_1") (pintype "passive"))
      (node (ref "R6") (pin "2") (pinfunction "2_2") (pintype "passive"))
      (node (ref "R8") (pin "1") (pinfunction "1_1") (pintype "passive"))
      (node (ref "U2") (pin "5") (pinfunction "VREF_5") (pintype "output"))
    )
    (net (code "76") (name "Net-(U3-C1+)") (class "Default")
      (node (ref "C6") (pin "2") (pinfunction "2_2") (pintype "passive"))
      (node (ref "U3") (pin "1") (pinfunction "C1+_1") (pintype "passive"))
    )
    (net (code "77") (name "Net-(U3-C1-)") (class "Default")
      (node (ref "C6") (pin "1") (pinfunction "1_1") (pintype "passive"))
      (node (ref "U3") (pin "3") (pinfunction "C1-_3") (pintype "passive"))
    )
    (net (code "78") (name "Net-(U3-C2+)") (class "Default")
      (node (ref "C9") (pin "2") (pinfunction "2_2") (pintype "passive"))
      (node (ref "U3") (pin "4") (pinfunction "C2+_4") (pintype "passive"))
    )
    (net (code "79") (name "Net-(U3-C2-)") (class "Default")
      (node (ref "C9") (pin "1") (pinfunction "1_1") (pintype "passive"))
      (node (ref "U3") (pin "5") (pinfunction "C2-_5") (pintype "passive"))
    )
    (net (code "80") (name "Net-(U3-DOUT1)") (class "Default")
      (node (ref "J7") (pin "2") (pinfunction "2_2") (pintype "passive"))
      (node (ref "U3") (pin "14") (pinfunction "DOUT1_14") (pintype "output"))
    )
    (net (code "81") (name "Net-(U3-RIN1)") (class "Default")
      (node (ref "J7") (pin "3") (pinfunction "3_3") (pintype "passive"))
      (node (ref "U3") (pin "13") (pinfunction "RIN1_13") (pintype "input"))
    )
    (net (code "82") (name "Net-(U3-V+)") (class "Default")
      (node (ref "C7") (pin "2") (pinfunction "2_2") (pintype "passive"))
      (node (ref "U3") (pin "2") (pinfunction "V+_2") (pintype "output"))
    )
    (net (code "83") (name "Net-(U3-V-)") (class "Default")
      (node (ref "C8") (pin "2") (pinfunction "2_2") (pintype "passive"))
      (node (ref "U3") (pin "6") (pinfunction "V-_6") (pintype "output"))
    )
    (net (code "84") (name "VCC_PWM") (class "Default")
      (node (ref "J10") (pin "4") (pinfunction "4_4") (pintype "passive"))
      (node (ref "J13") (pin "1") (pinfunction "1_1") (pintype "passive"))
      (node (ref "J14") (pin "1") (pinfunction "1_1") (pintype "passive"))
      (node (ref "J17") (pin "1") (pinfunction "1_1") (pintype "passive"))
      (node (ref "J18") (pin "1") (pinfunction "1_1") (pintype "passive"))
      (node (ref "J21") (pin "1") (pinfunction "1_1") (pintype "passive"))
      (node (ref "J22") (pin "1") (pinfunction "1_1") (pintype "passive"))
      (node (ref "J8") (pin "1") (pinfunction "1_1") (pintype "passive"))
      (node (ref "J9") (pin "1") (pinfunction "1_1") (pintype "passive"))
      (node (ref "R9") (pin "2") (pinfunction "2_2") (pintype "passive"))
    )
    (net (code "85") (name "VIN") (class "Default")
      (node (ref "J1") (pin "24") (pinfunction "24_24") (pintype "passive"))
      (node (ref "J31") (pin "2") (pinfunction "POS_2") (pintype "passive"))
      (node (ref "R10") (pin "1") (pinfunction "1_1") (pintype "passive"))
    )
    (net (code "86") (name "unconnected-(J1-Pad05)") (class "Default")
      (node (ref "J1") (pin "05") (pinfunction "05_05") (pintype "passive+no_connect"))
    )
    (net (code "87") (name "unconnected-(J1-Pad06)") (class "Default")
      (node (ref "J1") (pin "06") (pinfunction "06_06") (pintype "passive"))
    )
    (net (code "88") (name "unconnected-(J1-Pad07)") (class "Default")
      (node (ref "J1") (pin "07") (pinfunction "07_07") (pintype "passive+no_connect"))
    )
    (net (code "89") (name "unconnected-(J1-Pad10)") (class "Default")
      (node (ref "J1") (pin "10") (pinfunction "10_10") (pintype "passive+no_connect"))
    )
    (net (code "90") (name "unconnected-(J1-Pad12)") (class "Default")
      (node (ref "J1") (pin "12") (pinfunction "12_12") (pintype "passive"))
    )
    (net (code "91") (name "unconnected-(J1-Pad13)") (class "Default")
      (node (ref "J1") (pin "13") (pinfunction "13_13") (pintype "passive+no_connect"))
    )
    (net (code "92") (name "unconnected-(J1-Pad14)") (class "Default")
      (node (ref "J1") (pin "14") (pinfunction "14_14") (pintype "passive"))
    )
    (net (code "93") (name "unconnected-(J1-Pad15)") (class "Default")
      (node (ref "J1") (pin "15") (pinfunction "15_15") (pintype "passive+no_connect"))
    )
    (net (code "94") (name "unconnected-(J1-Pad17)") (class "Default")
      (node (ref "J1") (pin "17") (pinfunction "17_17") (pintype "passive+no_connect"))
    )
    (net (code "95") (name "unconnected-(J1-Pad21)") (class "Default")
      (node (ref "J1") (pin "21") (pinfunction "21_21") (pintype "passive+no_connect"))
    )
    (net (code "96") (name "unconnected-(J1-Pad23)") (class "Default")
      (node (ref "J1") (pin "23") (pinfunction "23_23") (pintype "passive+no_connect"))
    )
    (net (code "97") (name "unconnected-(J1-Pad25)") (class "Default")
      (node (ref "J1") (pin "25") (pinfunction "25_25") (pintype "passive+no_connect"))
    )
    (net (code "98") (name "unconnected-(J1-Pad26)") (class "Default")
      (node (ref "J1") (pin "26") (pinfunction "26_26") (pintype "passive+no_connect"))
    )
    (net (code "99") (name "unconnected-(J1-Pad27)") (class "Default")
      (node (ref "J1") (pin "27") (pinfunction "27_27") (pintype "passive+no_connect"))
    )
    (net (code "100") (name "unconnected-(J1-Pad28)") (class "Default")
      (node (ref "J1") (pin "28") (pinfunction "28_28") (pintype "passive+no_connect"))
    )
    (net (code "101") (name "unconnected-(J1-Pad29)") (class "Default")
      (node (ref "J1") (pin "29") (pinfunction "29_29") (pintype "passive+no_connect"))
    )
    (net (code "102") (name "unconnected-(J1-Pad30)") (class "Default")
      (node (ref "J1") (pin "30") (pinfunction "30_30") (pintype "passive+no_connect"))
    )
    (net (code "103") (name "unconnected-(J1-Pad31)") (class "Default")
      (node (ref "J1") (pin "31") (pinfunction "31_31") (pintype "passive+no_connect"))
    )
    (net (code "104") (name "unconnected-(J1-Pad33)") (class "Default")
      (node (ref "J1") (pin "33") (pinfunction "33_33") (pintype "passive+no_connect"))
    )
    (net (code "105") (name "unconnected-(J1-Pad34)") (class "Default")
      (node (ref "J1") (pin "34") (pinfunction "34_34") (pintype "passive+no_connect"))
    )
    (net (code "106") (name "unconnected-(J1-Pad36)") (class "Default")
      (node (ref "J1") (pin "36") (pinfunction "36_36") (pintype "passive+no_connect"))
    )
    (net (code "107") (name "unconnected-(J1-Pad39)") (class "Default")
      (node (ref "J1") (pin "39") (pinfunction "39_39") (pintype "passive+no_connect"))
    )
    (net (code "108") (name "unconnected-(J1-Pad41)") (class "Default")
      (node (ref "J1") (pin "41") (pinfunction "41_41") (pintype "passive+no_connect"))
    )
    (net (code "109") (name "unconnected-(J1-Pad42)") (class "Default")
      (node (ref "J1") (pin "42") (pinfunction "42_42") (pintype "passive+no_connect"))
    )
    (net (code "110") (name "unconnected-(J1-Pad44)") (class "Default")
      (node (ref "J1") (pin "44") (pinfunction "44_44") (pintype "passive+no_connect"))
    )
    (net (code "111") (name "unconnected-(J1-Pad47)") (class "Default")
      (node (ref "J1") (pin "47") (pinfunction "47_47") (pintype "passive+no_connect"))
    )
    (net (code "112") (name "unconnected-(J1-Pad52)") (class "Default")
      (node (ref "J1") (pin "52") (pinfunction "52_52") (pintype "passive+no_connect"))
    )
    (net (code "113") (name "unconnected-(J1-Pad58)") (class "Default")
      (node (ref "J1") (pin "58") (pinfunction "58_58") (pintype "passive+no_connect"))
    )
    (net (code "114") (name "unconnected-(J1-Pad59)") (class "Default")
      (node (ref "J1") (pin "59") (pinfunction "59_59") (pintype "passive+no_connect"))
    )
    (net (code "115") (name "unconnected-(J1-Pad64)") (class "Default")
      (node (ref "J1") (pin "64") (pinfunction "64_64") (pintype "passive+no_connect"))
    )
    (net (code "116") (name "unconnected-(J1-Pad67)") (class "Default")
      (node (ref "J1") (pin "67") (pinfunction "67_67") (pintype "passive+no_connect"))
    )
    (net (code "117") (name "unconnected-(J1-Pad69)") (class "Default")
      (node (ref "J1") (pin "69") (pinfunction "69_69") (pintype "passive+no_connect"))
    )
    (net (code "118") (name "unconnected-(J2-Pad02)") (class "Default")
      (node (ref "J2") (pin "02") (pinfunction "02_02") (pintype "passive+no_connect"))
    )
    (net (code "119") (name "unconnected-(J2-Pad04)") (class "Default")
      (node (ref "J2") (pin "04") (pinfunction "04_04") (pintype "passive+no_connect"))
    )
    (net (code "120") (name "unconnected-(J2-Pad06)") (class "Default")
      (node (ref "J2") (pin "06") (pinfunction "06_06") (pintype "passive+no_connect"))
    )
    (net (code "121") (name "unconnected-(J2-Pad07)") (class "Default")
      (node (ref "J2") (pin "07") (pinfunction "07_07") (pintype "passive+no_connect"))
    )
    (net (code "122") (name "unconnected-(J2-Pad08)") (class "Default")
      (node (ref "J2") (pin "08") (pinfunction "08_08") (pintype "passive+no_connect"))
    )
    (net (code "123") (name "unconnected-(J2-Pad10)") (class "Default")
      (node (ref "J2") (pin "10") (pinfunction "10_10") (pintype "passive+no_connect"))
    )
    (net (code "124") (name "unconnected-(J2-Pad12)") (class "Default")
      (node (ref "J2") (pin "12") (pinfunction "12_12") (pintype "passive+no_connect"))
    )
    (net (code "125") (name "unconnected-(J2-Pad14)") (class "Default")
      (node (ref "J2") (pin "14") (pinfunction "14_14") (pintype "passive+no_connect"))
    )
    (net (code "126") (name "unconnected-(J2-Pad15)") (class "Default")
      (node (ref "J2") (pin "15") (pinfunction "15_15") (pintype "passive+no_connect"))
    )
    (net (code "127") (name "unconnected-(J2-Pad16)") (class "Default")
      (node (ref "J2") (pin "16") (pinfunction "16_16") (pintype "passive+no_connect"))
    )
    (net (code "128") (name "unconnected-(J2-Pad18)") (class "Default")
      (node (ref "J2") (pin "18") (pinfunction "18_18") (pintype "passive+no_connect"))
    )
    (net (code "129") (name "unconnected-(J2-Pad21)") (class "Default")
      (node (ref "J2") (pin "21") (pinfunction "21_21") (pintype "passive+no_connect"))
    )
    (net (code "130") (name "unconnected-(J2-Pad22)") (class "Default")
      (node (ref "J2") (pin "22") (pinfunction "22_22") (pintype "passive+no_connect"))
    )
    (net (code "131") (name "unconnected-(J2-Pad26)") (class "Default")
      (node (ref "J2") (pin "26") (pinfunction "26_26") (pintype "passive+no_connect"))
    )
    (net (code "132") (name "unconnected-(J2-Pad28)") (class "Default")
      (node (ref "J2") (pin "28") (pinfunction "28_28") (pintype "passive+no_connect"))
    )
    (net (code "133") (name "unconnected-(J2-Pad30)") (class "Default")
      (node (ref "J2") (pin "30") (pinfunction "30_30") (pintype "passive+no_connect"))
    )
    (net (code "134") (name "unconnected-(J2-Pad32)") (class "Default")
      (node (ref "J2") (pin "32") (pinfunction "32_32") (pintype "passive+no_connect"))
    )
    (net (code "135") (name "unconnected-(J2-Pad34)") (class "Default")
      (node (ref "J2") (pin "34") (pinfunction "34_34") (pintype "passive+no_connect"))
    )
    (net (code "136") (name "unconnected-(J2-Pad45)") (class "Default")
      (node (ref "J2") (pin "45") (pinfunction "45_45") (pintype "passive+no_connect"))
    )
    (net (code "137") (name "unconnected-(J2-Pad46)") (class "Default")
      (node (ref "J2") (pin "46") (pinfunction "46_46") (pintype "passive+no_connect"))
    )
    (net (code "138") (name "unconnected-(J2-Pad47)") (class "Default")
      (node (ref "J2") (pin "47") (pinfunction "47_47") (pintype "passive+no_connect"))
    )
    (net (code "139") (name "unconnected-(J2-Pad48)") (class "Default")
      (node (ref "J2") (pin "48") (pinfunction "48_48") (pintype "passive+no_connect"))
    )
    (net (code "140") (name "unconnected-(J2-Pad49)") (class "Default")
      (node (ref "J2") (pin "49") (pinfunction "49_49") (pintype "passive+no_connect"))
    )
    (net (code "141") (name "unconnected-(J2-Pad52)") (class "Default")
      (node (ref "J2") (pin "52") (pinfunction "52_52") (pintype "passive+no_connect"))
    )
    (net (code "142") (name "unconnected-(J2-Pad53)") (class "Default")
      (node (ref "J2") (pin "53") (pinfunction "53_53") (pintype "passive+no_connect"))
    )
    (net (code "143") (name "unconnected-(J2-Pad56)") (class "Default")
      (node (ref "J2") (pin "56") (pinfunction "56_56") (pintype "passive+no_connect"))
    )
    (net (code "144") (name "unconnected-(J2-Pad62)") (class "Default")
      (node (ref "J2") (pin "62") (pinfunction "62_62") (pintype "passive+no_connect"))
    )
    (net (code "145") (name "unconnected-(J2-Pad65)") (class "Default")
      (node (ref "J2") (pin "65") (pinfunction "65_65") (pintype "passive+no_connect"))
    )
    (net (code "146") (name "unconnected-(J2-Pad67)") (class "Default")
      (node (ref "J2") (pin "67") (pinfunction "67_67") (pintype "passive+no_connect"))
    )
    (net (code "147") (name "unconnected-(J2-Pad68)") (class "Default")
      (node (ref "J2") (pin "68") (pinfunction "68_68") (pintype "passive+no_connect"))
    )
    (net (code "148") (name "unconnected-(J2-Pad69)") (class "Default")
      (node (ref "J2") (pin "69") (pinfunction "69_69") (pintype "passive+no_connect"))
    )
    (net (code "149") (name "unconnected-(J2-Pad70)") (class "Default")
      (node (ref "J2") (pin "70") (pinfunction "70_70") (pintype "passive+no_connect"))
    )
    (net (code "150") (name "unconnected-(J3-Pad1)") (class "Default")
      (node (ref "J3") (pin "1") (pinfunction "1_1") (pintype "passive"))
    )
    (net (code "151") (name "unconnected-(J3-Pad3)") (class "Default")
      (node (ref "J3") (pin "3") (pinfunction "3_3") (pintype "passive"))
    )
    (net (code "152") (name "unconnected-(J3-Pad4)") (class "Default")
      (node (ref "J3") (pin "4") (pinfunction "4_4") (pintype "passive"))
    )
    (net (code "153") (name "unconnected-(J3-Pad5)") (class "Default")
      (node (ref "J3") (pin "5") (pinfunction "5_5") (pintype "passive"))
    )
    (net (code "154") (name "unconnected-(J3-Pad6)") (class "Default")
      (node (ref "J3") (pin "6") (pinfunction "6_6") (pintype "passive"))
    )
    (net (code "155") (name "unconnected-(J3-Pad8)") (class "Default")
      (node (ref "J3") (pin "8") (pinfunction "8_8") (pintype "passive"))
    )
    (net (code "156") (name "unconnected-(J3-Pad9)") (class "Default")
      (node (ref "J3") (pin "9") (pinfunction "9_9") (pintype "passive"))
    )
    (net (code "157") (name "unconnected-(J4-Pad1)") (class "Default")
      (node (ref "J4") (pin "1") (pinfunction "1_1") (pintype "passive"))
    )
    (net (code "158") (name "unconnected-(J4-Pad3)") (class "Default")
      (node (ref "J4") (pin "3") (pinfunction "3_3") (pintype "passive"))
    )
    (net (code "159") (name "unconnected-(J4-Pad4)") (class "Default")
      (node (ref "J4") (pin "4") (pinfunction "4_4") (pintype "passive"))
    )
    (net (code "160") (name "unconnected-(J4-Pad5)") (class "Default")
      (node (ref "J4") (pin "5") (pinfunction "5_5") (pintype "passive"))
    )
    (net (code "161") (name "unconnected-(J4-Pad6)") (class "Default")
      (node (ref "J4") (pin "6") (pinfunction "6_6") (pintype "passive"))
    )
    (net (code "162") (name "unconnected-(J4-Pad8)") (class "Default")
      (node (ref "J4") (pin "8") (pinfunction "8_8") (pintype "passive"))
    )
    (net (code "163") (name "unconnected-(J4-Pad9)") (class "Default")
      (node (ref "J4") (pin "9") (pinfunction "9_9") (pintype "passive"))
    )
    (net (code "164") (name "unconnected-(J7-Pad1)") (class "Default")
      (node (ref "J7") (pin "1") (pinfunction "1_1") (pintype "passive"))
    )
    (net (code "165") (name "unconnected-(J7-Pad4)") (class "Default")
      (node (ref "J7") (pin "4") (pinfunction "4_4") (pintype "passive"))
    )
    (net (code "166") (name "unconnected-(J7-Pad6)") (class "Default")
      (node (ref "J7") (pin "6") (pinfunction "6_6") (pintype "passive"))
    )
    (net (code "167") (name "unconnected-(J7-Pad7)") (class "Default")
      (node (ref "J7") (pin "7") (pinfunction "7_7") (pintype "passive"))
    )
    (net (code "168") (name "unconnected-(J7-Pad8)") (class "Default")
      (node (ref "J7") (pin "8") (pinfunction "8_8") (pintype "passive"))
    )
    (net (code "169") (name "unconnected-(J7-Pad9)") (class "Default")
      (node (ref "J7") (pin "9") (pinfunction "9_9") (pintype "passive"))
    )
    (net (code "170") (name "unconnected-(J10-Pad5)") (class "Default")
      (node (ref "J10") (pin "5") (pinfunction "5_5") (pintype "passive"))
    )
    (net (code "171") (name "unconnected-(U3-DIN2-Pad10)") (class "Default")
      (node (ref "U3") (pin "10") (pinfunction "DIN2_10") (pintype "input+no_connect"))
    )
    (net (code "172") (name "unconnected-(U3-DOUT2-Pad7)") (class "Default")
      (node (ref "U3") (pin "7") (pinfunction "DOUT2_7") (pintype "output+no_connect"))
    )
    (net (code "173") (name "unconnected-(U3-RIN2-Pad8)") (class "Default")
      (node (ref "U3") (pin "8") (pinfunction "RIN2_8") (pintype "input+no_connect"))
    )
    (net (code "174") (name "unconnected-(U3-ROUT2-Pad9)") (class "Default")
      (node (ref "U3") (pin "9") (pinfunction "ROUT2_9") (pintype "output+no_connect"))
    )
  )
)
